# V1.net
KiCad netlist of a schematic drawn in EAGLE
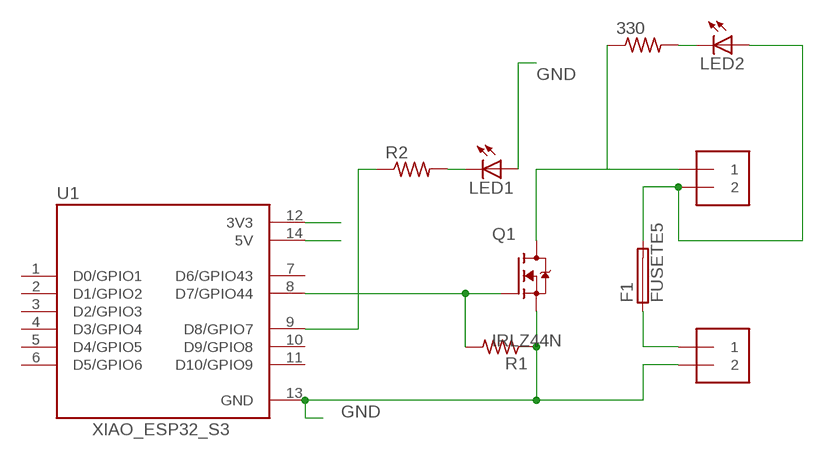
[diagram p0: schematic, sheet 1]

(export (version "E")
  (design (tool "Eeschema 10.0.6"))
  (components
    (comp (ref "330")
      (value "R-US_0204/7")
      (footprint "eagle-import:0204_7")
      (libsource (lib "eagle-import") (part "R-US_0204/7"))
    )
    (comp (ref "F1")
      (value "FUSETE5")
      (footprint "eagle-import:TE5")
      (libsource (lib "eagle-import") (part "FUSETE5"))
    )
    (comp (ref "J1")
      (value "1X2-3.5MM")
      (footprint "eagle-import:1X2-3.5MM")
      (libsource (lib "eagle-import") (part "1X2-3.5MM"))
    )
    (comp (ref "J2")
      (value "1X2-3.5MM")
      (footprint "eagle-import:1X2-3.5MM")
      (libsource (lib "eagle-import") (part "1X2-3.5MM"))
    )
    (comp (ref "LED1")
      (value "LED5MM")
      (footprint "eagle-import:LED5MM")
      (libsource (lib "eagle-import") (part "LED5MM"))
    )
    (comp (ref "LED2")
      (value "LED5MM")
      (footprint "eagle-import:LED5MM")
      (libsource (lib "eagle-import") (part "LED5MM"))
    )
    (comp (ref "Q1")
      (value "IRLZ44N")
      (footprint "eagle-import:TO254P1054X469X1930-3")
      (fields (field (name "MF") "Infineon Technologies"))
      (libsource (lib "eagle-import") (part "IRLZ44N"))
    )
    (comp (ref "R1")
      (value "R-US_0204/7")
      (footprint "eagle-import:0204_7")
      (libsource (lib "eagle-import") (part "R-US_0204/7"))
    )
    (comp (ref "R2")
      (value "R-US_0204/7")
      (footprint "eagle-import:0204_7")
      (libsource (lib "eagle-import") (part "R-US_0204/7"))
    )
    (comp (ref "U1")
      (value "XIAO_ESP32_S3")
      (footprint "eagle-import:MODULE_XIAO_ESP32_S3")
      (fields (field (name "MF") "Seeed Studio") (field (name "MP") "XIAO ESP32 S3"))
      (libsource (lib "eagle-import") (part "XIAO_ESP32_S3"))
    )
  )
  (nets
    (net (code "1") (name "/GND") (class "Default")
      (node (ref "J2") (pin "2") (pinfunction "2_2") (pintype "passive"))
      (node (ref "LED1") (pin "A") (pinfunction "A_A") (pintype "passive"))
      (node (ref "Q1") (pin "3") (pinfunction "S_3") (pintype "passive"))
      (node (ref "R1") (pin "1") (pinfunction "1_1") (pintype "passive"))
      (node (ref "U1") (pin "13") (pinfunction "GND_13") (pintype "power_in"))
    )
    (net (code "2") (name "Net-(F1-Pad1)") (class "Default")
      (node (ref "F1") (pin "1") (pinfunction "1_1") (pintype "passive"))
      (node (ref "J2") (pin "1") (pinfunction "1_1") (pintype "passive"))
    )
    (net (code "3") (name "Net-(F1-Pad2)") (class "Default")
      (node (ref "F1") (pin "2") (pinfunction "2_2") (pintype "passive"))
      (node (ref "J1") (pin "2") (pinfunction "2_2") (pintype "passive"))
      (node (ref "LED2") (pin "A") (pinfunction "A_A") (pintype "passive"))
    )
    (net (code "4") (name "Net-(LED1-C)") (class "Default")
      (node (ref "LED1") (pin "K") (pinfunction "C_K") (pintype "passive"))
      (node (ref "R2") (pin "2") (pinfunction "2_2") (pintype "passive"))
    )
    (net (code "5") (name "Net-(LED2-C)") (class "Default")
      (node (ref "330") (pin "2") (pinfunction "2_2") (pintype "passive"))
      (node (ref "LED2") (pin "K") (pinfunction "C_K") (pintype "passive"))
    )
    (net (code "6") (name "Net-(Q1-D)") (class "Default")
      (node (ref "330") (pin "1") (pinfunction "1_1") (pintype "passive"))
      (node (ref "J1") (pin "1") (pinfunction "1_1") (pintype "passive"))
      (node (ref "Q1") (pin "2") (pinfunction "D_2") (pintype "passive"))
    )
    (net (code "7") (name "Net-(Q1-G)") (class "Default")
      (node (ref "Q1") (pin "1") (pinfunction "G_1") (pintype "passive"))
      (node (ref "R1") (pin "2") (pinfunction "2_2") (pintype "passive"))
      (node (ref "U1") (pin "8") (pinfunction "D7/GPIO44_8") (pintype "bidirectional"))
    )
    (net (code "8") (name "Net-(U1-D8{slash}GPIO7)") (class "Default")
      (node (ref "R2") (pin "1") (pinfunction "1_1") (pintype "passive"))
      (node (ref "U1") (pin "9") (pinfunction "D8/GPIO7_9") (pintype "bidirectional"))
    )
    (net (code "9") (name "unconnected-(U1-3V3-Pad12)") (class "Default")
      (node (ref "U1") (pin "12") (pinfunction "3V3_12") (pintype "power_in"))
    )
    (net (code "10") (name "unconnected-(U1-5V-Pad14)") (class "Default")
      (node (ref "U1") (pin "14") (pinfunction "5V_14") (pintype "power_in"))
    )
    (net (code "11") (name "unconnected-(U1-D0{slash}GPIO1-Pad1)") (class "Default")
      (node (ref "U1") (pin "1") (pinfunction "D0/GPIO1_1") (pintype "bidirectional"))
    )
    (net (code "12") (name "unconnected-(U1-D1{slash}GPIO2-Pad2)") (class "Default")
      (node (ref "U1") (pin "2") (pinfunction "D1/GPIO2_2") (pintype "bidirectional"))
    )
    (net (code "13") (name "unconnected-(U1-D2{slash}GPIO3-Pad3)") (class "Default")
      (node (ref "U1") (pin "3") (pinfunction "D2/GPIO3_3") (pintype "bidirectional"))
    )
    (net (code "14") (name "unconnected-(U1-D3{slash}GPIO4-Pad4)") (class "Default")
      (node (ref "U1") (pin "4") (pinfunction "D3/GPIO4_4") (pintype "bidirectional"))
    )
    (net (code "15") (name "unconnected-(U1-D4{slash}GPIO5-Pad5)") (class "Default")
      (node (ref "U1") (pin "5") (pinfunction "D4/GPIO5_5") (pintype "bidirectional"))
    )
    (net (code "16") (name "unconnected-(U1-D5{slash}GPIO6-Pad6)") (class "Default")
      (node (ref "U1") (pin "6") (pinfunction "D5/GPIO6_6") (pintype "bidirectional"))
    )
    (net (code "17") (name "unconnected-(U1-D6{slash}GPIO43-Pad7)") (class "Default")
      (node (ref "U1") (pin "7") (pinfunction "D6/GPIO43_7") (pintype "bidirectional"))
    )
    (net (code "18") (name "unconnected-(U1-D9{slash}GPIO8-Pad10)") (class "Default")
      (node (ref "U1") (pin "10") (pinfunction "D9/GPIO8_10") (pintype "bidirectional"))
    )
    (net (code "19") (name "unconnected-(U1-D10{slash}GPIO9-Pad11)") (class "Default")
      (node (ref "U1") (pin "11") (pinfunction "D10/GPIO9_11") (pintype "bidirectional"))
    )
  )
)
